# ESP_12F_2x8_pinout.net
KiCad netlist of a schematic drawn in EAGLE
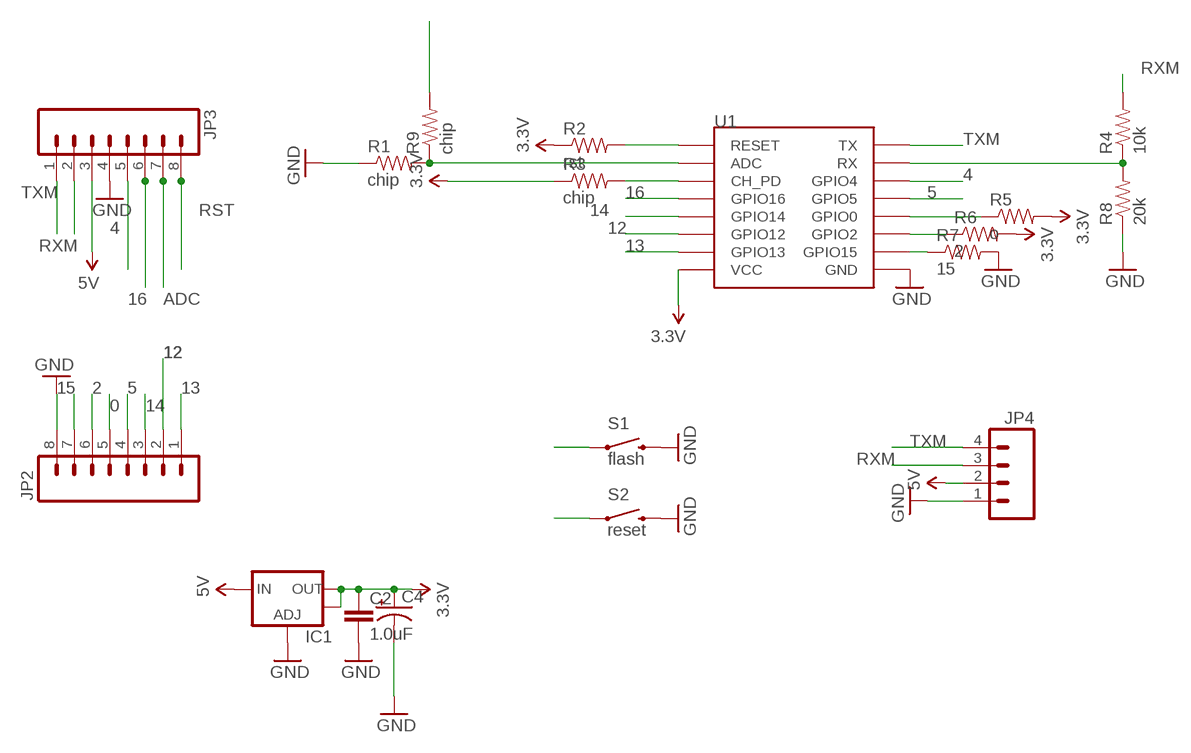
[diagram p0: schematic, sheet 1]

(export (version "E")
  (design (tool "Eeschema 10.0.6"))
  (components
    (comp (ref "C2")
      (value "1.0uF")
      (footprint "eagle-import:1206")
      (libsource (lib "eagle-import") (part "1.0UF50V10%(1206)"))
    )
    (comp (ref "C4")
      (value "47UF-50V-20%(ELECT)")
      (footprint "eagle-import:PANASONIC_D")
      (libsource (lib "eagle-import") (part "47UF-50V-20%(ELECT)"))
    )
    (comp (ref "IC1")
      (value "V_REG_LM1117SOT223")
      (footprint "eagle-import:SOT223")
      (libsource (lib "eagle-import") (part "V_REG_LM1117SOT223"))
    )
    (comp (ref "JP2")
      (value "M08")
      (footprint "eagle-import:1X08_ROUND")
      (libsource (lib "eagle-import") (part "M08"))
    )
    (comp (ref "JP3")
      (value "M08")
      (footprint "eagle-import:1X08_ROUND")
      (libsource (lib "eagle-import") (part "M08"))
    )
    (comp (ref "JP4")
      (value "M04PTH")
      (footprint "eagle-import:1X04")
      (libsource (lib "eagle-import") (part "M04PTH"))
    )
    (comp (ref "R1")
      (value "chip")
      (footprint "eagle-import:0805")
      (libsource (lib "eagle-import") (part "0.3OHM-1/8W-1%(0805)"))
    )
    (comp (ref "R2")
      (value "rst")
      (footprint "eagle-import:0805")
      (libsource (lib "eagle-import") (part "0.3OHM-1/8W-1%(0805)"))
    )
    (comp (ref "R3")
      (value "chip")
      (footprint "eagle-import:0805")
      (libsource (lib "eagle-import") (part "0.3OHM-1/8W-1%(0805)"))
    )
    (comp (ref "R4")
      (value "10k")
      (footprint "eagle-import:0805")
      (libsource (lib "eagle-import") (part "0.3OHM-1/8W-1%(0805)"))
    )
    (comp (ref "R5")
      (value "o")
      (footprint "eagle-import:0805")
      (libsource (lib "eagle-import") (part "0.3OHM-1/8W-1%(0805)"))
    )
    (comp (ref "R6")
      (value "2")
      (footprint "eagle-import:0805")
      (libsource (lib "eagle-import") (part "0.3OHM-1/8W-1%(0805)"))
    )
    (comp (ref "R7")
      (value "15")
      (footprint "eagle-import:0805")
      (libsource (lib "eagle-import") (part "0.3OHM-1/8W-1%(0805)"))
    )
    (comp (ref "R8")
      (value "20k")
      (footprint "eagle-import:0805")
      (libsource (lib "eagle-import") (part "0.3OHM-1/8W-1%(0805)"))
    )
    (comp (ref "R9")
      (value "chip")
      (footprint "eagle-import:0805")
      (libsource (lib "eagle-import") (part "0.3OHM-1/8W-1%(0805)"))
    )
    (comp (ref "S1")
      (value "flash")
      (footprint "eagle-import:TACTILE-SWITCH-1101NE")
      (libsource (lib "eagle-import") (part "SWITCH-MOMENTARY-2SMD-1101NE"))
    )
    (comp (ref "S2")
      (value "reset")
      (footprint "eagle-import:TACTILE-SWITCH-1101NE")
      (libsource (lib "eagle-import") (part "SWITCH-MOMENTARY-2SMD-1101NE"))
    )
    (comp (ref "U1")
      (value "ESP12SMD")
      (footprint "eagle-import:ESP12-SMD")
      (libsource (lib "eagle-import") (part "ESP12SMD"))
    )
  )
  (nets
    (net (code "1") (name "/0") (class "Default")
      (node (ref "JP2") (pin "5") (pinfunction "5_5") (pintype "passive"))
      (node (ref "R5") (pin "1") (pinfunction "1_1") (pintype "passive"))
      (node (ref "S1") (pin "1") (pinfunction "1_1") (pintype "passive"))
      (node (ref "U1") (pin "GPIO0") (pinfunction "GPIO0_GPIO0") (pintype "bidirectional"))
    )
    (net (code "2") (name "/2") (class "Default")
      (node (ref "JP2") (pin "6") (pinfunction "6_6") (pintype "passive"))
      (node (ref "R6") (pin "1") (pinfunction "1_1") (pintype "passive"))
      (node (ref "U1") (pin "GPIO2") (pinfunction "GPIO2_GPIO2") (pintype "bidirectional"))
    )
    (net (code "3") (name "/4") (class "Default")
      (node (ref "JP3") (pin "5") (pinfunction "5_5") (pintype "passive"))
      (node (ref "U1") (pin "GPIO4") (pinfunction "GPIO4_GPIO4") (pintype "bidirectional"))
    )
    (net (code "4") (name "/5") (class "Default")
      (node (ref "JP2") (pin "4") (pinfunction "4_4") (pintype "passive"))
      (node (ref "U1") (pin "GPIO5") (pinfunction "GPIO5_GPIO5") (pintype "bidirectional"))
    )
    (net (code "5") (name "/12") (class "Default")
      (node (ref "JP2") (pin "2") (pinfunction "2_2") (pintype "passive"))
      (node (ref "U1") (pin "GPIO12") (pinfunction "GPIO12_GPIO12") (pintype "bidirectional"))
    )
    (net (code "6") (name "/13") (class "Default")
      (node (ref "JP2") (pin "1") (pinfunction "1_1") (pintype "passive"))
      (node (ref "U1") (pin "GPIO13") (pinfunction "GPIO13_GPIO13") (pintype "bidirectional"))
    )
    (net (code "7") (name "/14") (class "Default")
      (node (ref "JP2") (pin "3") (pinfunction "3_3") (pintype "passive"))
      (node (ref "U1") (pin "GPIO14") (pinfunction "GPIO14_GPIO14") (pintype "bidirectional"))
    )
    (net (code "8") (name "/15") (class "Default")
      (node (ref "JP2") (pin "7") (pinfunction "7_7") (pintype "passive"))
      (node (ref "R7") (pin "1") (pinfunction "1_1") (pintype "passive"))
      (node (ref "U1") (pin "GPIO15") (pinfunction "GPIO15_GPIO15") (pintype "bidirectional"))
    )
    (net (code "9") (name "/16") (class "Default")
      (node (ref "JP3") (pin "6") (pinfunction "6_6") (pintype "passive"))
      (node (ref "U1") (pin "GPIO16") (pinfunction "GPIO16_GPIO16") (pintype "bidirectional"))
    )
    (net (code "10") (name "/ADC") (class "Default")
      (node (ref "JP3") (pin "7") (pinfunction "7_7") (pintype "passive"))
      (node (ref "R9") (pin "2") (pinfunction "2_2") (pintype "passive"))
    )
    (net (code "11") (name "/RST") (class "Default")
      (node (ref "JP3") (pin "8") (pinfunction "8_8") (pintype "passive"))
      (node (ref "R2") (pin "2") (pinfunction "2_2") (pintype "passive"))
      (node (ref "S2") (pin "1") (pinfunction "1_1") (pintype "passive"))
      (node (ref "U1") (pin "RESET") (pinfunction "RESET_RESET") (pintype "bidirectional"))
    )
    (net (code "12") (name "/RXM") (class "Default")
      (node (ref "JP3") (pin "2") (pinfunction "2_2") (pintype "passive"))
      (node (ref "JP4") (pin "3") (pinfunction "3_3") (pintype "passive"))
      (node (ref "R4") (pin "2") (pinfunction "2_2") (pintype "passive"))
    )
    (net (code "13") (name "/TXM") (class "Default")
      (node (ref "JP3") (pin "1") (pinfunction "1_1") (pintype "passive"))
      (node (ref "JP4") (pin "4") (pinfunction "4_4") (pintype "passive"))
      (node (ref "U1") (pin "TXD0") (pinfunction "TX_TXD0") (pintype "bidirectional"))
    )
    (net (code "14") (name "3.3V") (class "Default")
      (node (ref "C2") (pin "1") (pinfunction "1_1") (pintype "passive"))
      (node (ref "C4") (pin "+") (pinfunction "+_+") (pintype "passive"))
      (node (ref "IC1") (pin "2") (pinfunction "OUT_2") (pintype "output"))
      (node (ref "IC1") (pin "4") (pinfunction "OUT_4") (pintype "output"))
      (node (ref "R2") (pin "1") (pinfunction "1_1") (pintype "passive"))
      (node (ref "R3") (pin "1") (pinfunction "1_1") (pintype "passive"))
      (node (ref "R5") (pin "2") (pinfunction "2_2") (pintype "passive"))
      (node (ref "R6") (pin "2") (pinfunction "2_2") (pintype "passive"))
      (node (ref "U1") (pin "VCC") (pinfunction "VCC_VCC") (pintype "bidirectional"))
    )
    (net (code "15") (name "5V") (class "Default")
      (node (ref "IC1") (pin "3") (pinfunction "IN_3") (pintype "input"))
      (node (ref "JP3") (pin "3") (pinfunction "3_3") (pintype "passive"))
      (node (ref "JP4") (pin "2") (pinfunction "2_2") (pintype "passive"))
    )
    (net (code "16") (name "GND") (class "Default")
      (node (ref "C2") (pin "2") (pinfunction "2_2") (pintype "passive"))
      (node (ref "C4") (pin "-") (pinfunction "-_-") (pintype "passive"))
      (node (ref "IC1") (pin "1") (pinfunction "ADJ_1") (pintype "input"))
      (node (ref "JP2") (pin "8") (pinfunction "8_8") (pintype "passive"))
      (node (ref "JP3") (pin "4") (pinfunction "4_4") (pintype "passive"))
      (node (ref "JP4") (pin "1") (pinfunction "1_1") (pintype "passive"))
      (node (ref "R1") (pin "1") (pinfunction "1_1") (pintype "passive"))
      (node (ref "R7") (pin "2") (pinfunction "2_2") (pintype "passive"))
      (node (ref "R8") (pin "1") (pinfunction "1_1") (pintype "passive"))
      (node (ref "S1") (pin "2") (pinfunction "2_2") (pintype "passive"))
      (node (ref "S2") (pin "2") (pinfunction "2_2") (pintype "passive"))
      (node (ref "U1") (pin "GND") (pinfunction "GND_GND") (pintype "bidirectional"))
    )
    (net (code "17") (name "Net-(R1-Pad2)") (class "Default")
      (node (ref "R1") (pin "2") (pinfunction "2_2") (pintype "passive"))
      (node (ref "R9") (pin "1") (pinfunction "1_1") (pintype "passive"))
      (node (ref "U1") (pin "ADC") (pinfunction "ADC_ADC") (pintype "bidirectional"))
    )
    (net (code "18") (name "Net-(R3-Pad2)") (class "Default")
      (node (ref "R3") (pin "2") (pinfunction "2_2") (pintype "passive"))
      (node (ref "U1") (pin "CH_PD") (pinfunction "CH_PD_CH_PD") (pintype "bidirectional"))
    )
    (net (code "19") (name "Net-(U1-RX)") (class "Default")
      (node (ref "R4") (pin "1") (pinfunction "1_1") (pintype "passive"))
      (node (ref "R8") (pin "2") (pinfunction "2_2") (pintype "passive"))
      (node (ref "U1") (pin "RXD0") (pinfunction "RX_RXD0") (pintype "bidirectional"))
    )
  )
)
